# ADC.net
KiCad netlist of a schematic drawn in Altium Designer
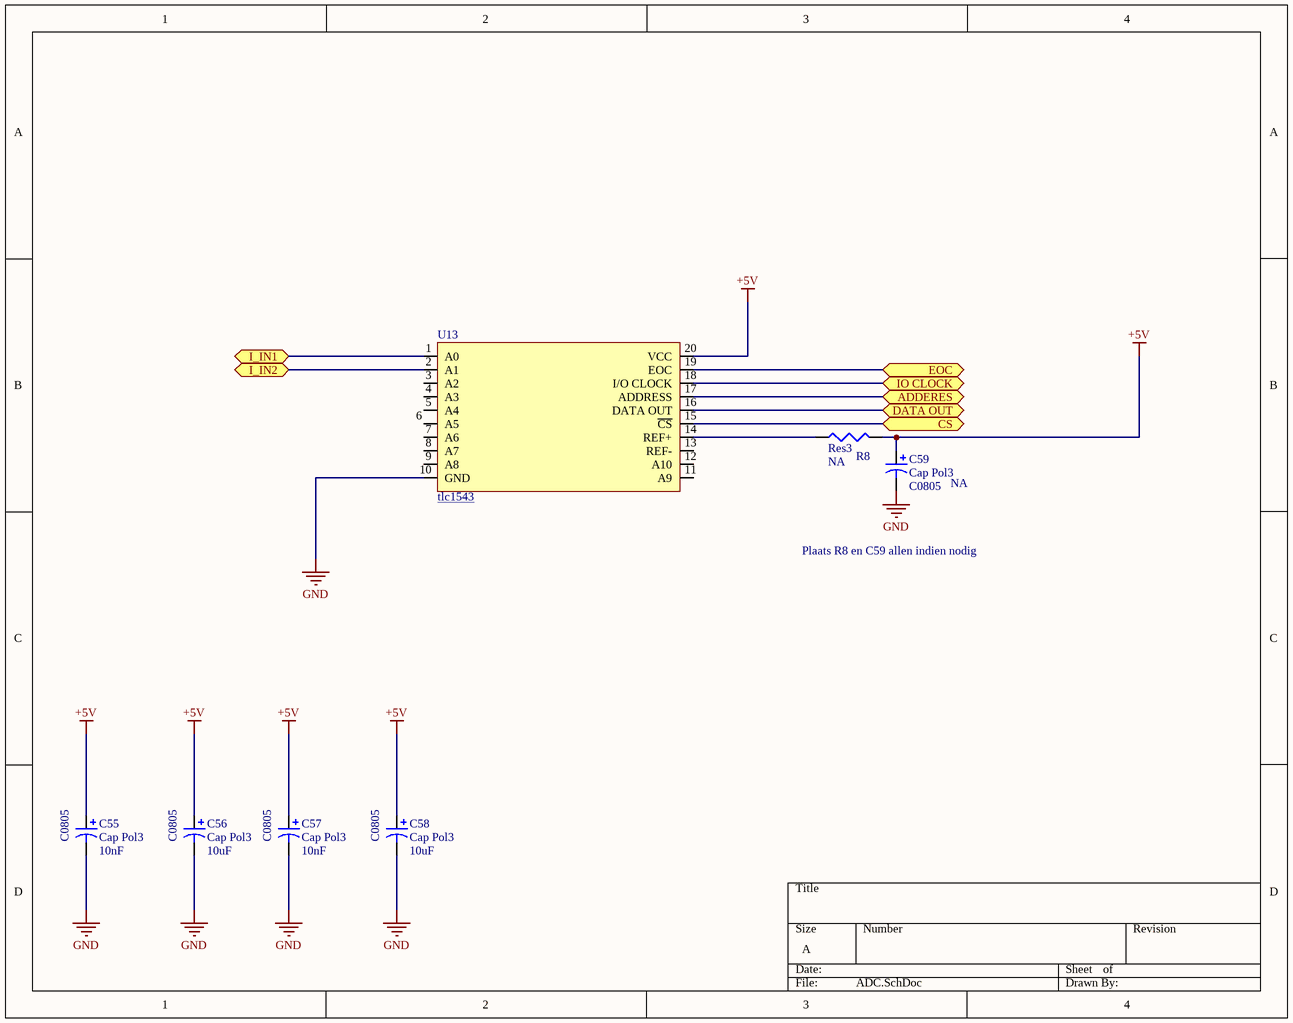
[diagram p0: ADC.SchDoc]

(export (version "E")
  (design (tool "Eeschema 10.0.6"))
  (components
    (comp (ref "C55")
      (value "Cap Pol3")
      (footprint "C0805")
      (description "Polarized Capacitor (Surface Mount)")
      (fields
        (field (name "PACKAGEREFERENCE") "C0805")
        (field (name "ALTIUM_VALUE") "10nF")
        (field (name "PUBLISHER") "Altium Limited")
      )
      (libsource (lib "Miscellaneous Devices") (part "Cap Pol3"))
    )
    (comp (ref "C56")
      (value "Cap Pol3")
      (footprint "C0805")
      (description "Polarized Capacitor (Surface Mount)")
      (fields
        (field (name "PACKAGEREFERENCE") "C0805")
        (field (name "ALTIUM_VALUE") "10uF")
        (field (name "PUBLISHER") "Altium Limited")
      )
      (libsource (lib "Miscellaneous Devices") (part "Cap Pol3"))
    )
    (comp (ref "C57")
      (value "Cap Pol3")
      (footprint "C0805")
      (description "Polarized Capacitor (Surface Mount)")
      (fields
        (field (name "PACKAGEREFERENCE") "C0805")
        (field (name "ALTIUM_VALUE") "10nF")
        (field (name "PUBLISHER") "Altium Limited")
      )
      (libsource (lib "Miscellaneous Devices") (part "Cap Pol3"))
    )
    (comp (ref "C58")
      (value "Cap Pol3")
      (footprint "C0805")
      (description "Polarized Capacitor (Surface Mount)")
      (fields
        (field (name "PACKAGEREFERENCE") "C0805")
        (field (name "ALTIUM_VALUE") "10uF")
        (field (name "PUBLISHER") "Altium Limited")
      )
      (libsource (lib "Miscellaneous Devices") (part "Cap Pol3"))
    )
    (comp (ref "C59")
      (value "Cap Pol3")
      (footprint "C0805")
      (description "Polarized Capacitor (Surface Mount)")
      (fields
        (field (name "PACKAGEREFERENCE") "C0805")
        (field (name "ALTIUM_VALUE") "NA")
        (field (name "PUBLISHER") "Altium Limited")
      )
      (libsource (lib "Miscellaneous Devices") (part "Cap Pol3"))
    )
    (comp (ref "R8")
      (value "Res3")
      (footprint "J1-0603")
      (description "Resistor")
      (fields (field (name "ALTIUM_VALUE") "NA") (field (name "PUBLISHER") "Altium Limited"))
      (libsource (lib "Miscellaneous Devices") (part "Res3"))
    )
    (comp (ref "U13")
      (value "tlc1543")
      (footprint "tlc1543")
      (libsource (lib "TLC1543CDWG4") (part "tlc1543"))
    )
  )
  (nets
    (net (code "1") (name "+5V") (class "Default")
      (node (ref "C55") (pin "1") (pinfunction "1_1") (pintype "passive"))
      (node (ref "C56") (pin "1") (pinfunction "1_1") (pintype "passive"))
      (node (ref "C57") (pin "1") (pinfunction "1_1") (pintype "passive"))
      (node (ref "C58") (pin "1") (pinfunction "1_1") (pintype "passive"))
      (node (ref "C59") (pin "1") (pinfunction "1_1") (pintype "passive"))
      (node (ref "R8") (pin "2") (pinfunction "2_2") (pintype "passive"))
      (node (ref "U13") (pin "20") (pinfunction "VCC_20") (pintype "passive"))
    )
    (net (code "2") (name "/ADDERES") (class "Default")
      (node (ref "U13") (pin "17") (pinfunction "ADDRESS_17") (pintype "passive"))
    )
    (net (code "3") (name "/CS") (class "Default")
      (node (ref "U13") (pin "15") (pinfunction "~{CS}_15") (pintype "passive"))
    )
    (net (code "4") (name "/DATA OUT") (class "Default")
      (node (ref "U13") (pin "16") (pinfunction "DATA_OUT_16") (pintype "passive"))
    )
    (net (code "5") (name "/EOC") (class "Default")
      (node (ref "U13") (pin "19") (pinfunction "EOC_19") (pintype "passive"))
    )
    (net (code "6") (name "/IO CLOCK") (class "Default")
      (node (ref "U13") (pin "18") (pinfunction "I/O_CLOCK_18") (pintype "passive"))
    )
    (net (code "7") (name "/I_IN1") (class "Default")
      (node (ref "U13") (pin "1") (pinfunction "A0_1") (pintype "passive"))
    )
    (net (code "8") (name "/I_IN2") (class "Default")
      (node (ref "U13") (pin "2") (pinfunction "A1_2") (pintype "passive"))
    )
    (net (code "9") (name "GND") (class "Default")
      (node (ref "C55") (pin "2") (pinfunction "2_2") (pintype "passive"))
      (node (ref "C56") (pin "2") (pinfunction "2_2") (pintype "passive"))
      (node (ref "C57") (pin "2") (pinfunction "2_2") (pintype "passive"))
      (node (ref "C58") (pin "2") (pinfunction "2_2") (pintype "passive"))
      (node (ref "C59") (pin "2") (pinfunction "2_2") (pintype "passive"))
      (node (ref "U13") (pin "10") (pinfunction "GND_10") (pintype "passive"))
    )
    (net (code "10") (name "Net-(U13-REF+)") (class "Default")
      (node (ref "R8") (pin "1") (pinfunction "1_1") (pintype "passive"))
      (node (ref "U13") (pin "14") (pinfunction "REF+_14") (pintype "passive"))
    )
    (net (code "11") (name "unconnected-(U13-A2-Pad3)") (class "Default")
      (node (ref "U13") (pin "3") (pinfunction "A2_3") (pintype "passive"))
    )
    (net (code "12") (name "unconnected-(U13-A3-Pad4)") (class "Default")
      (node (ref "U13") (pin "4") (pinfunction "A3_4") (pintype "passive"))
    )
    (net (code "13") (name "unconnected-(U13-A4-Pad5)") (class "Default")
      (node (ref "U13") (pin "5") (pinfunction "A4_5") (pintype "passive"))
    )
    (net (code "14") (name "unconnected-(U13-A5-Pad6)") (class "Default")
      (node (ref "U13") (pin "6") (pinfunction "A5_6") (pintype "passive"))
    )
    (net (code "15") (name "unconnected-(U13-A6-Pad7)") (class "Default")
      (node (ref "U13") (pin "7") (pinfunction "A6_7") (pintype "passive"))
    )
    (net (code "16") (name "unconnected-(U13-A7-Pad8)") (class "Default")
      (node (ref "U13") (pin "8") (pinfunction "A7_8") (pintype "passive"))
    )
    (net (code "17") (name "unconnected-(U13-A8-Pad9)") (class "Default")
      (node (ref "U13") (pin "9") (pinfunction "A8_9") (pintype "passive"))
    )
    (net (code "18") (name "unconnected-(U13-A9-Pad11)") (class "Default")
      (node (ref "U13") (pin "11") (pinfunction "A9_11") (pintype "passive"))
    )
    (net (code "19") (name "unconnected-(U13-A10-Pad12)") (class "Default")
      (node (ref "U13") (pin "12") (pinfunction "A10_12") (pintype "passive"))
    )
    (net (code "20") (name "unconnected-(U13-REF--Pad13)") (class "Default")
      (node (ref "U13") (pin "13") (pinfunction "REF-_13") (pintype "passive"))
    )
  )
)
